# rotary_encoder_1_0.net
KiCad netlist of a schematic drawn in EAGLE
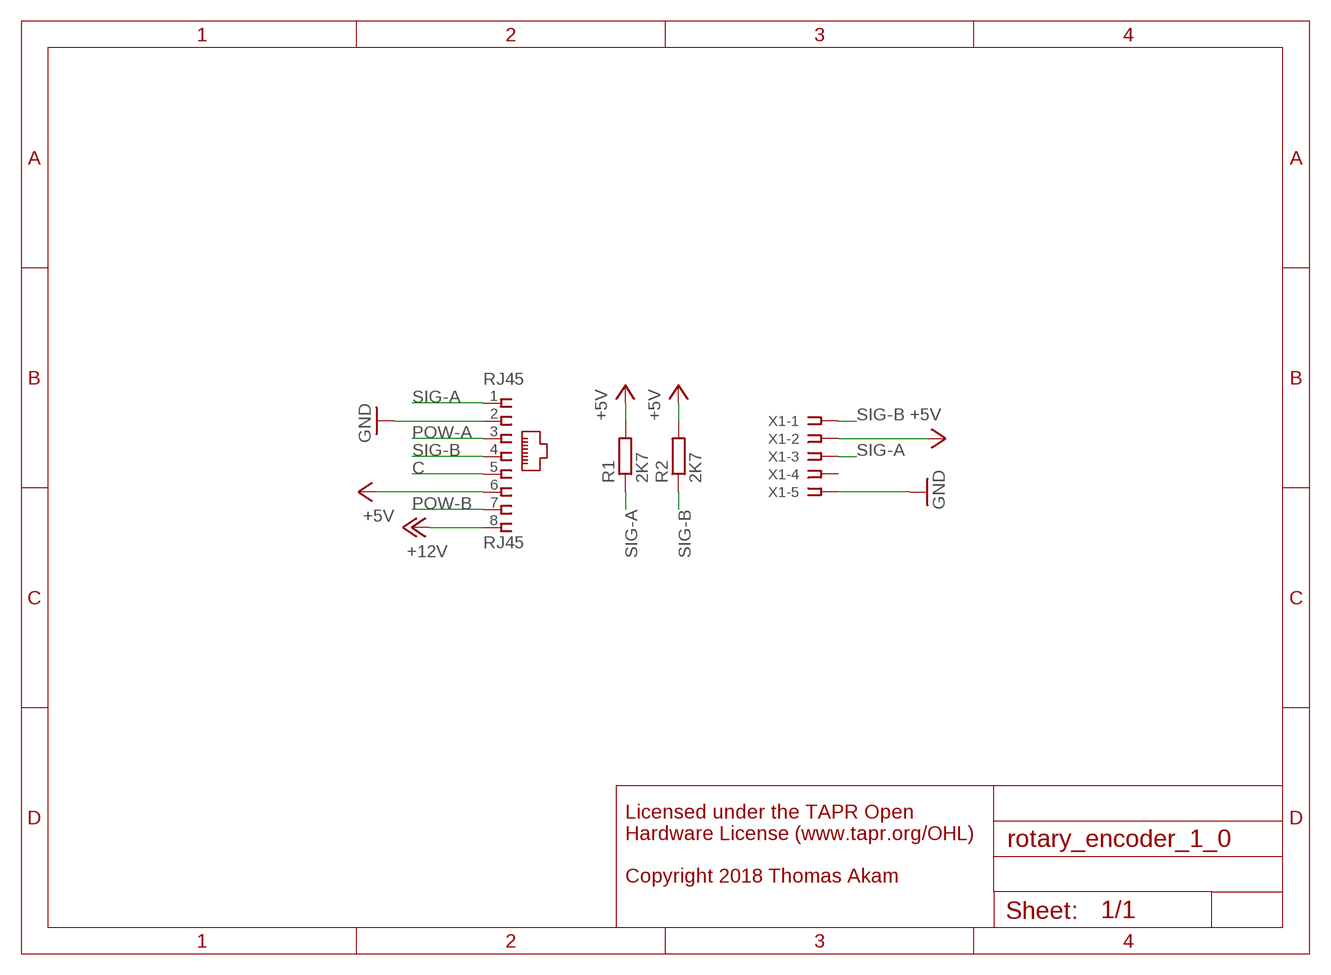
[diagram p0: schematic, sheet 1]

(export (version "E")
  (design (tool "Eeschema 10.0.6"))
  (components
    (comp (ref "R1")
      (value "2K7")
      (footprint "eagle-import:M0805")
      (libsource (lib "eagle-import") (part "R-EU_M0805"))
    )
    (comp (ref "R2")
      (value "2K7")
      (footprint "eagle-import:M0805")
      (libsource (lib "eagle-import") (part "R-EU_M0805"))
    )
    (comp (ref "RJ45")
      (value "RJ45")
      (footprint "eagle-import:RJ45-NO-SHIELD-VERTICAL")
      (libsource (lib "eagle-import") (part "RJ45VERTICAL"))
    )
    (comp (ref "X1")
      (value "SSW-105-02-S-S-RA")
      (footprint "eagle-import:SSW-105-02-S-S-RA")
      (libsource (lib "eagle-import") (part "SSW-105-02-S-S-RA"))
    )
  )
  (nets
    (net (code "1") (name "+5V") (class "Default")
      (node (ref "R1") (pin "2") (pinfunction "2_2") (pintype "passive"))
      (node (ref "R2") (pin "2") (pinfunction "2_2") (pintype "passive"))
      (node (ref "RJ45") (pin "6") (pinfunction "6_6") (pintype "passive"))
      (node (ref "X1") (pin "2") (pinfunction "1_2") (pintype "passive"))
    )
    (net (code "2") (name "+12V") (class "Default")
      (node (ref "RJ45") (pin "8") (pinfunction "8_8") (pintype "passive"))
    )
    (net (code "3") (name "/C") (class "Default")
      (node (ref "RJ45") (pin "5") (pinfunction "5_5") (pintype "passive"))
    )
    (net (code "4") (name "/POW-A") (class "Default")
      (node (ref "RJ45") (pin "3") (pinfunction "3_3") (pintype "passive"))
    )
    (net (code "5") (name "/POW-B") (class "Default")
      (node (ref "RJ45") (pin "7") (pinfunction "7_7") (pintype "passive"))
    )
    (net (code "6") (name "/SIG-A") (class "Default")
      (node (ref "R1") (pin "1") (pinfunction "1_1") (pintype "passive"))
      (node (ref "RJ45") (pin "1") (pinfunction "1_1") (pintype "passive"))
      (node (ref "X1") (pin "3") (pinfunction "1_3") (pintype "passive"))
    )
    (net (code "7") (name "/SIG-B") (class "Default")
      (node (ref "R2") (pin "1") (pinfunction "1_1") (pintype "passive"))
      (node (ref "RJ45") (pin "4") (pinfunction "4_4") (pintype "passive"))
      (node (ref "X1") (pin "1") (pinfunction "1_1") (pintype "passive"))
    )
    (net (code "8") (name "GND") (class "Default")
      (node (ref "RJ45") (pin "2") (pinfunction "2_2") (pintype "passive"))
      (node (ref "X1") (pin "5") (pinfunction "1_5") (pintype "passive"))
    )
    (net (code "9") (name "unconnected-(X1D-1-Pad4)") (class "Default")
      (node (ref "X1") (pin "4") (pinfunction "1_4") (pintype "passive"))
    )
  )
)
